# Sheet1.net
KiCad netlist of a schematic drawn in Altium Designer
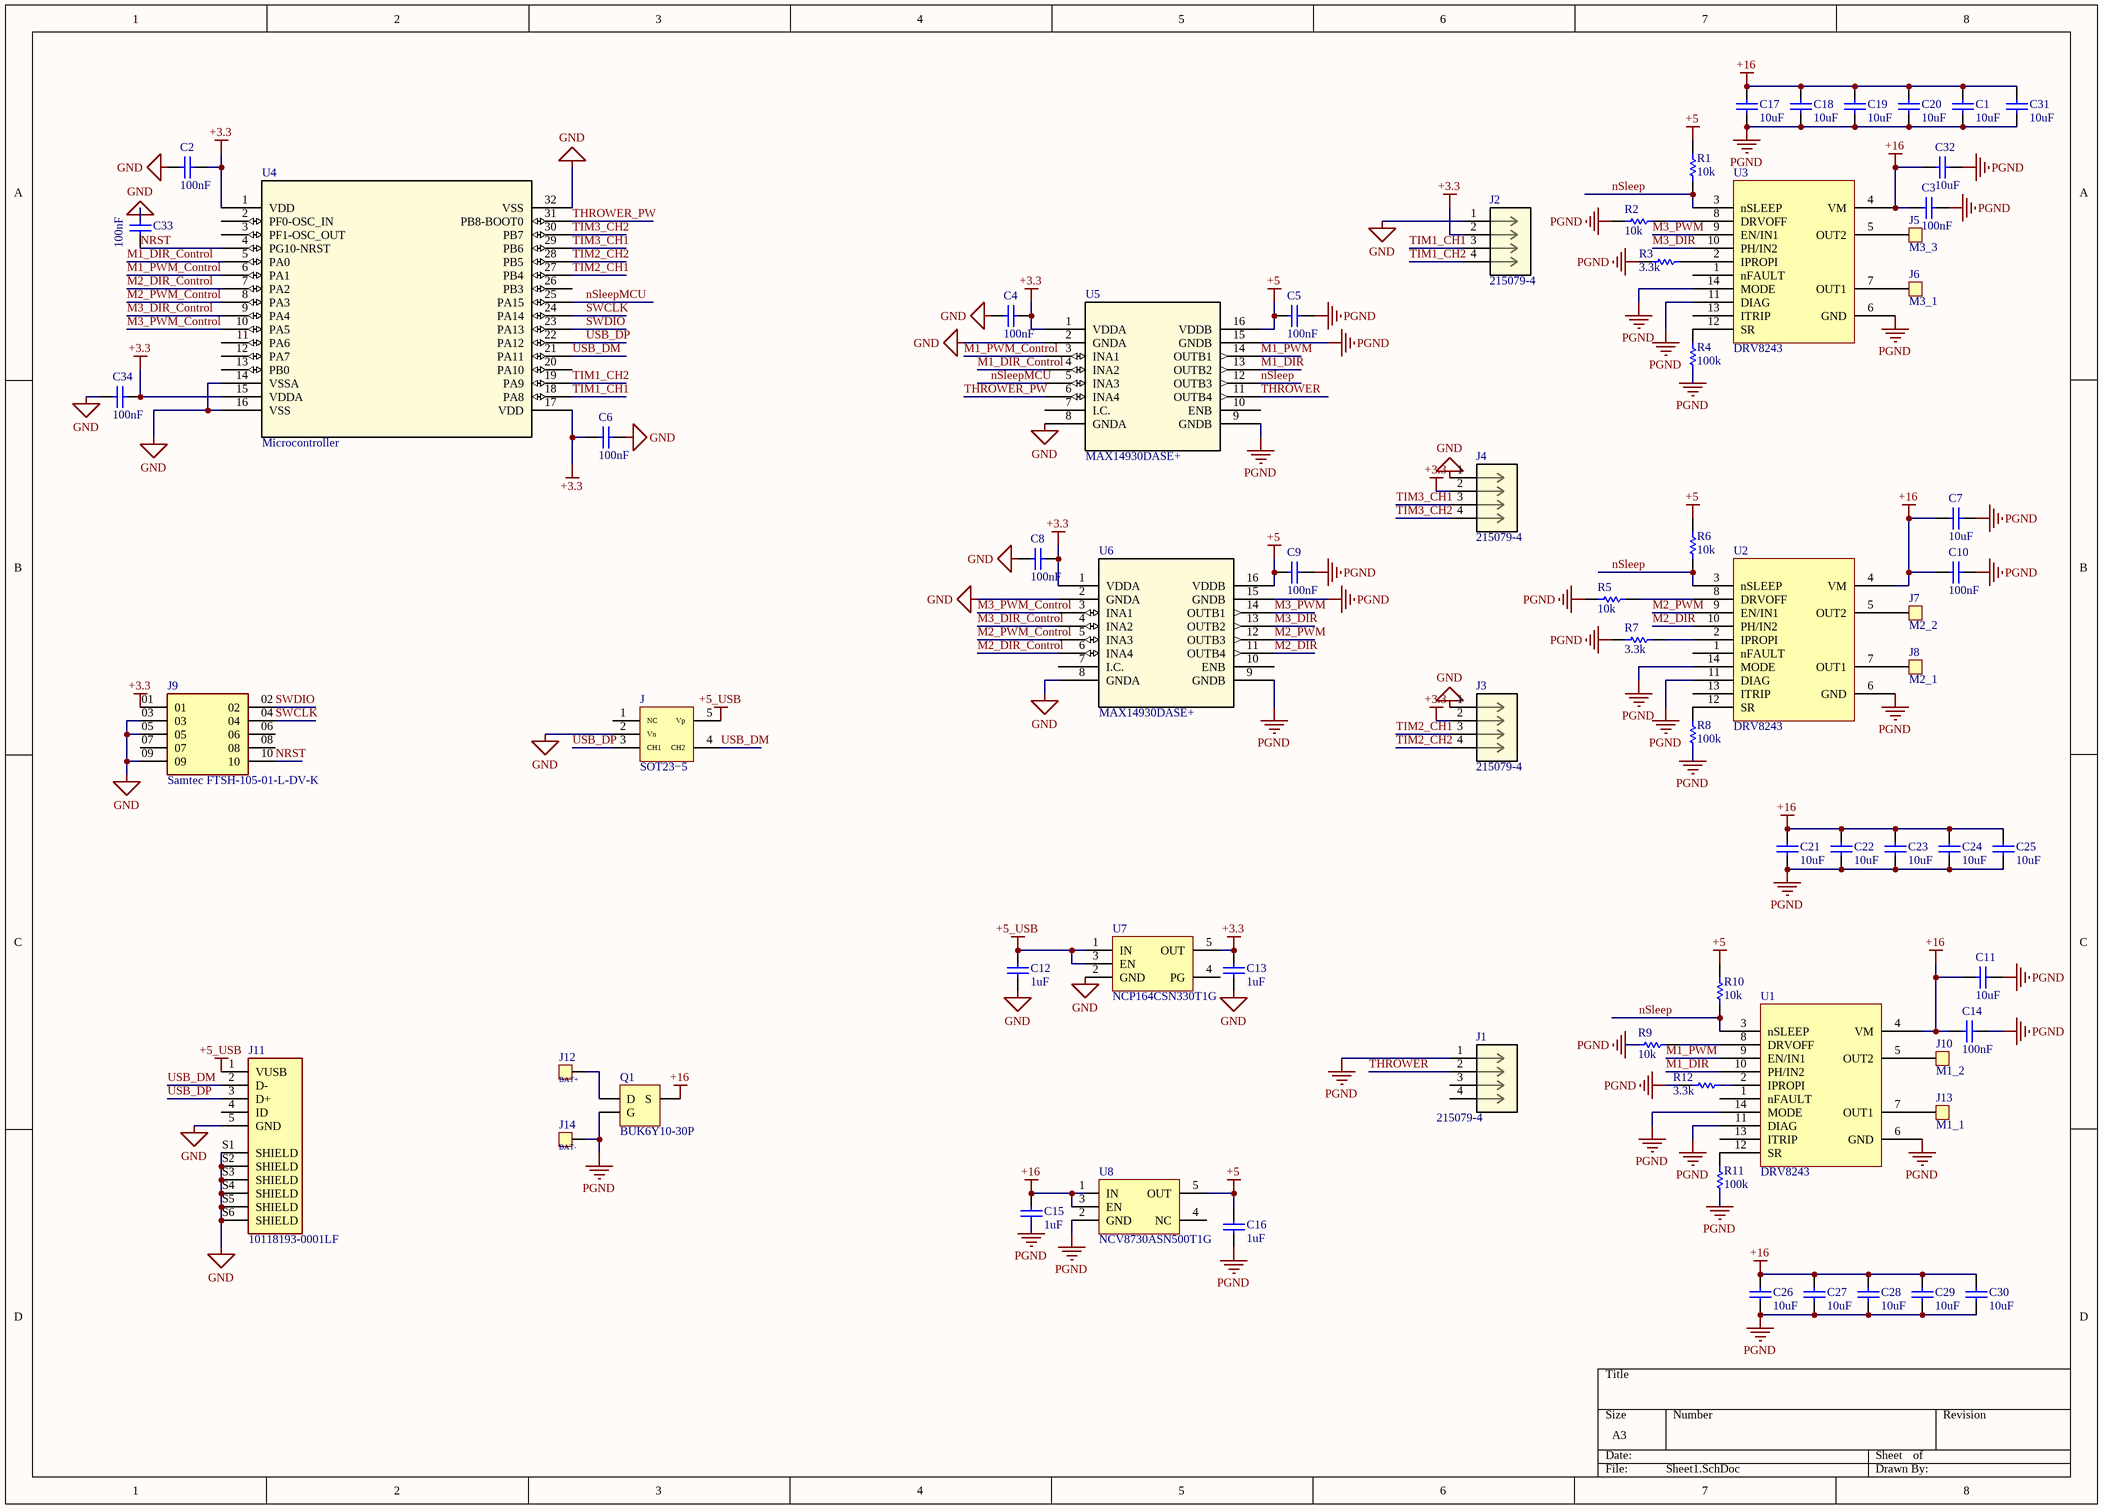
[diagram p0: Sheet1.SchDoc]

(export (version "E")
  (design (tool "Eeschema 10.0.6"))
  (components
    (comp (ref "C1")
      (value "10uF")
      (footprint "CAPC1206(3216)190_N")
      (description "CAP 10uF 25V -20% to +80% 1206 (3216 Metric) Thickness 1.9mm SMD")
      (fields (field (name "TOLERANCE") "-20% to +80%") (field (name "Comment") "CAP 10uF"))
      (libsource (lib "Altium Content Vault") (part "CAP"))
    )
    (comp (ref "C2")
      (value "100nF")
      (footprint "CAPC1608X90X35LL15T15")
      (fields
        (field (name "MANUFACTURER") "AVX Interconnect / Elco")
        (field (name "PART NUMBER") "06035C104J4Z2A")
      )
      (libsource (lib "Altium Content Vault") (part "CAP"))
    )
    (comp (ref "C3")
      (value "100nF")
      (footprint "CAPC1608X90X35LL15T15")
      (fields
        (field (name "MANUFACTURER") "AVX Interconnect / Elco")
        (field (name "PART NUMBER") "06035C104J4Z2A")
      )
      (libsource (lib "Altium Content Vault") (part "CAP"))
    )
    (comp (ref "C4")
      (value "100nF")
      (footprint "CAPC1608X90X35LL15T15")
      (fields
        (field (name "MANUFACTURER") "AVX Interconnect / Elco")
        (field (name "PART NUMBER") "06035C104J4Z2A")
      )
      (libsource (lib "Altium Content Vault") (part "CAP"))
    )
    (comp (ref "C5")
      (value "100nF")
      (footprint "CAPC1608X90X35LL15T15")
      (fields
        (field (name "MANUFACTURER") "AVX Interconnect / Elco")
        (field (name "PART NUMBER") "06035C104J4Z2A")
      )
      (libsource (lib "Altium Content Vault") (part "CAP"))
    )
    (comp (ref "C6")
      (value "100nF")
      (footprint "CAPC1608X90X35LL15T15")
      (fields
        (field (name "MANUFACTURER") "AVX Interconnect / Elco")
        (field (name "PART NUMBER") "06035C104J4Z2A")
      )
      (libsource (lib "Altium Content Vault") (part "CAP"))
    )
    (comp (ref "C7")
      (value "10uF")
      (footprint "CAPC1206(3216)190_N")
      (description "CAP 10uF 25V -20% to +80% 1206 (3216 Metric) Thickness 1.9mm SMD")
      (fields (field (name "TOLERANCE") "-20% to +80%") (field (name "Comment") "CAP 10uF"))
      (libsource (lib "Altium Content Vault") (part "CAP"))
    )
    (comp (ref "C8")
      (value "100nF")
      (footprint "CAPC1608X90X35LL15T15")
      (fields
        (field (name "MANUFACTURER") "AVX Interconnect / Elco")
        (field (name "PART NUMBER") "06035C104J4Z2A")
      )
      (libsource (lib "Altium Content Vault") (part "CAP"))
    )
    (comp (ref "C9")
      (value "100nF")
      (footprint "CAPC1608X90X35LL15T15")
      (fields
        (field (name "MANUFACTURER") "AVX Interconnect / Elco")
        (field (name "PART NUMBER") "06035C104J4Z2A")
      )
      (libsource (lib "Altium Content Vault") (part "CAP"))
    )
    (comp (ref "C10")
      (value "100nF")
      (footprint "CAPC1608X90X35LL15T15")
      (fields
        (field (name "MANUFACTURER") "AVX Interconnect / Elco")
        (field (name "PART NUMBER") "06035C104J4Z2A")
      )
      (libsource (lib "Altium Content Vault") (part "CAP"))
    )
    (comp (ref "C11")
      (value "10uF")
      (footprint "CAPC1206(3216)190_N")
      (description "CAP 10uF 25V -20% to +80% 1206 (3216 Metric) Thickness 1.9mm SMD")
      (fields (field (name "TOLERANCE") "-20% to +80%") (field (name "Comment") "CAP 10uF"))
      (libsource (lib "Altium Content Vault") (part "CAP"))
    )
    (comp (ref "C12")
      (value "1uF")
      (footprint "CAPC1608X90X35LL15T15")
      (fields
        (field (name "MANUFACTURER") "AVX Interconnect / Elco")
        (field (name "PART NUMBER") "06035C104J4Z2A")
      )
      (libsource (lib "Altium Content Vault") (part "CAP"))
    )
    (comp (ref "C13")
      (value "1uF")
      (footprint "CAPC1608X90X35LL15T15")
      (fields
        (field (name "MANUFACTURER") "AVX Interconnect / Elco")
        (field (name "PART NUMBER") "06035C104J4Z2A")
      )
      (libsource (lib "Altium Content Vault") (part "CAP"))
    )
    (comp (ref "C14")
      (value "100nF")
      (footprint "CAPC1608X90X35LL15T15")
      (fields
        (field (name "MANUFACTURER") "AVX Interconnect / Elco")
        (field (name "PART NUMBER") "06035C104J4Z2A")
      )
      (libsource (lib "Altium Content Vault") (part "CAP"))
    )
    (comp (ref "C15")
      (value "1uF")
      (footprint "CAPC1608X90X35LL15T15")
      (fields
        (field (name "MANUFACTURER") "AVX Interconnect / Elco")
        (field (name "PART NUMBER") "06035C104J4Z2A")
      )
      (libsource (lib "Altium Content Vault") (part "CAP"))
    )
    (comp (ref "C16")
      (value "1uF")
      (footprint "CAPC1608X90X35LL15T15")
      (fields
        (field (name "MANUFACTURER") "AVX Interconnect / Elco")
        (field (name "PART NUMBER") "06035C104J4Z2A")
      )
      (libsource (lib "Altium Content Vault") (part "CAP"))
    )
    (comp (ref "C17")
      (value "10uF")
      (footprint "CAPC1206(3216)190_N")
      (description "CAP 10uF 25V -20% to +80% 1206 (3216 Metric) Thickness 1.9mm SMD")
      (fields (field (name "TOLERANCE") "-20% to +80%") (field (name "Comment") "CAP 10uF"))
      (libsource (lib "Altium Content Vault") (part "CAP"))
    )
    (comp (ref "C18")
      (value "10uF")
      (footprint "CAPC1206(3216)190_N")
      (description "CAP 10uF 25V -20% to +80% 1206 (3216 Metric) Thickness 1.9mm SMD")
      (fields (field (name "TOLERANCE") "-20% to +80%") (field (name "Comment") "CAP 10uF"))
      (libsource (lib "Altium Content Vault") (part "CAP"))
    )
    (comp (ref "C19")
      (value "10uF")
      (footprint "CAPC1206(3216)190_N")
      (description "CAP 10uF 25V -20% to +80% 1206 (3216 Metric) Thickness 1.9mm SMD")
      (fields (field (name "TOLERANCE") "-20% to +80%") (field (name "Comment") "CAP 10uF"))
      (libsource (lib "Altium Content Vault") (part "CAP"))
    )
    (comp (ref "C20")
      (value "10uF")
      (footprint "CAPC1206(3216)190_N")
      (description "CAP 10uF 25V -20% to +80% 1206 (3216 Metric) Thickness 1.9mm SMD")
      (fields (field (name "TOLERANCE") "-20% to +80%") (field (name "Comment") "CAP 10uF"))
      (libsource (lib "Altium Content Vault") (part "CAP"))
    )
    (comp (ref "C21")
      (value "10uF")
      (footprint "CAPC1206(3216)190_N")
      (description "CAP 10uF 25V -20% to +80% 1206 (3216 Metric) Thickness 1.9mm SMD")
      (fields (field (name "TOLERANCE") "-20% to +80%") (field (name "Comment") "CAP 10uF"))
      (libsource (lib "Altium Content Vault") (part "CAP"))
    )
    (comp (ref "C22")
      (value "10uF")
      (footprint "CAPC1206(3216)190_N")
      (description "CAP 10uF 25V -20% to +80% 1206 (3216 Metric) Thickness 1.9mm SMD")
      (fields (field (name "TOLERANCE") "-20% to +80%") (field (name "Comment") "CAP 10uF"))
      (libsource (lib "Altium Content Vault") (part "CAP"))
    )
    (comp (ref "C23")
      (value "10uF")
      (footprint "CAPC1206(3216)190_N")
      (description "CAP 10uF 25V -20% to +80% 1206 (3216 Metric) Thickness 1.9mm SMD")
      (fields (field (name "TOLERANCE") "-20% to +80%") (field (name "Comment") "CAP 10uF"))
      (libsource (lib "Altium Content Vault") (part "CAP"))
    )
    (comp (ref "C24")
      (value "10uF")
      (footprint "CAPC1206(3216)190_N")
      (description "CAP 10uF 25V -20% to +80% 1206 (3216 Metric) Thickness 1.9mm SMD")
      (fields (field (name "TOLERANCE") "-20% to +80%") (field (name "Comment") "CAP 10uF"))
      (libsource (lib "Altium Content Vault") (part "CAP"))
    )
    (comp (ref "C25")
      (value "10uF")
      (footprint "CAPC1206(3216)190_N")
      (description "CAP 10uF 25V -20% to +80% 1206 (3216 Metric) Thickness 1.9mm SMD")
      (fields (field (name "TOLERANCE") "-20% to +80%") (field (name "Comment") "CAP 10uF"))
      (libsource (lib "Altium Content Vault") (part "CAP"))
    )
    (comp (ref "C26")
      (value "10uF")
      (footprint "CAPC1206(3216)190_N")
      (description "CAP 10uF 25V -20% to +80% 1206 (3216 Metric) Thickness 1.9mm SMD")
      (fields (field (name "TOLERANCE") "-20% to +80%") (field (name "Comment") "CAP 10uF"))
      (libsource (lib "Altium Content Vault") (part "CAP"))
    )
    (comp (ref "C27")
      (value "10uF")
      (footprint "CAPC1206(3216)190_N")
      (description "CAP 10uF 25V -20% to +80% 1206 (3216 Metric) Thickness 1.9mm SMD")
      (fields (field (name "TOLERANCE") "-20% to +80%") (field (name "Comment") "CAP 10uF"))
      (libsource (lib "Altium Content Vault") (part "CAP"))
    )
    (comp (ref "C28")
      (value "10uF")
      (footprint "CAPC1206(3216)190_N")
      (description "CAP 10uF 25V -20% to +80% 1206 (3216 Metric) Thickness 1.9mm SMD")
      (fields (field (name "TOLERANCE") "-20% to +80%") (field (name "Comment") "CAP 10uF"))
      (libsource (lib "Altium Content Vault") (part "CAP"))
    )
    (comp (ref "C29")
      (value "10uF")
      (footprint "CAPC1206(3216)190_N")
      (description "CAP 10uF 25V -20% to +80% 1206 (3216 Metric) Thickness 1.9mm SMD")
      (fields (field (name "TOLERANCE") "-20% to +80%") (field (name "Comment") "CAP 10uF"))
      (libsource (lib "Altium Content Vault") (part "CAP"))
    )
    (comp (ref "C30")
      (value "10uF")
      (footprint "CAPC1206(3216)190_N")
      (description "CAP 10uF 25V -20% to +80% 1206 (3216 Metric) Thickness 1.9mm SMD")
      (fields (field (name "TOLERANCE") "-20% to +80%") (field (name "Comment") "CAP 10uF"))
      (libsource (lib "Altium Content Vault") (part "CAP"))
    )
    (comp (ref "C31")
      (value "10uF")
      (footprint "CAPC1206(3216)190_N")
      (description "CAP 10uF 25V -20% to +80% 1206 (3216 Metric) Thickness 1.9mm SMD")
      (fields (field (name "TOLERANCE") "-20% to +80%") (field (name "Comment") "CAP 10uF"))
      (libsource (lib "Altium Content Vault") (part "CAP"))
    )
    (comp (ref "C32")
      (value "10uF")
      (footprint "CAPC1608X90X35LL15T15")
      (fields
        (field (name "MANUFACTURER") "AVX Interconnect / Elco")
        (field (name "PART NUMBER") "06035C104J4Z2A")
      )
      (libsource (lib "Altium Content Vault") (part "CAP"))
    )
    (comp (ref "C33")
      (value "100nF")
      (footprint "CAPC1608X90X35LL15T15")
      (fields
        (field (name "MANUFACTURER") "AVX Interconnect / Elco")
        (field (name "PART NUMBER") "06035C104J4Z2A")
      )
      (libsource (lib "Altium Content Vault") (part "CAP"))
    )
    (comp (ref "C34")
      (value "100nF")
      (footprint "CAPC1608X90X35LL15T15")
      (fields
        (field (name "MANUFACTURER") "AVX Interconnect / Elco")
        (field (name "PART NUMBER") "06035C104J4Z2A")
      )
      (libsource (lib "Altium Content Vault") (part "CAP"))
    )
    (comp (ref "J")
      (value "SOT23−5")
      (footprint "CM1223-02SO")
      (description "USB protection")
      (libsource (lib "Schlib1") (part "CM1223-02SO TVS diode array"))
    )
    (comp (ref "J1")
      (value "215079-4")
      (footprint "Micro-MaTch 215079-4")
      (description "Thrower ESC connector")
      (libsource (lib "Schlib1") (part "Micro-MaTch 215079-4_1"))
    )
    (comp (ref "J2")
      (value "215079-4")
      (footprint "Micro-MaTch 215079-4")
      (description "Encoder connectors")
      (libsource (lib "Schlib1") (part "Micro-MaTch 215079-4_1"))
    )
    (comp (ref "J3")
      (value "215079-4")
      (footprint "Micro-MaTch 215079-4")
      (description "Encoder connectors")
      (libsource (lib "Schlib1") (part "Micro-MaTch 215079-4_1"))
    )
    (comp (ref "J4")
      (value "215079-4")
      (footprint "Micro-MaTch 215079-4")
      (description "Encoder connectors")
      (libsource (lib "Schlib1") (part "Micro-MaTch 215079-4_1"))
    )
    (comp (ref "J5") (value "M3_3") (footprint "J") (libsource (lib "Schlib1") (part "J")))
    (comp (ref "J6") (value "M3_1") (footprint "J") (libsource (lib "Schlib1") (part "J")))
    (comp (ref "J7") (value "M2_2") (footprint "J") (libsource (lib "Schlib1") (part "J")))
    (comp (ref "J8") (value "M2_1") (footprint "J") (libsource (lib "Schlib1") (part "J")))
    (comp (ref "J9")
      (value "Samtec FTSH-105-01-L-DV-K")
      (footprint "Samtec FTSH-105-01-L-DV-K")
      (description "Programmer connector")
      (libsource (lib "Schlib1") (part "Samtec FTSH-105-01-L-DV-K"))
    )
    (comp (ref "J10") (value "M1_2") (footprint "J") (libsource (lib "Schlib1") (part "J")))
    (comp (ref "J11")
      (value "10118193-0001LF")
      (footprint "Amphenol 10118193-0001LF")
      (description "USB connector")
      (libsource (lib "Schlib1") (part "Amphenol 10118193-0001LF"))
    )
    (comp (ref "J12") (value "~") (footprint "J") (libsource (lib "") (part "J_1")))
    (comp (ref "J13") (value "M1_1") (footprint "J") (libsource (lib "Schlib1") (part "J")))
    (comp (ref "J14") (value "~") (footprint "J") (libsource (lib "") (part "J_1")))
    (comp (ref "Q1")
      (value "BUK6Y10-30P")
      (footprint "BUK6Y10-30P")
      (description "Reverse voltage protection")
      (libsource (lib "Schlib1") (part "BUK6Y10-30P"))
    )
    (comp (ref "R1")
      (value "ERJ3EKF1002V")
      (footprint "RESC1609X55X30LL15T15")
      (description "Chip Resistor, 10 KOhm, +/- 1%, 0.1 W, -55 to 155 degC, 0603 (1608 Metric), RoHS, Tape and Reel")
      (fields
        (field (name "RESISTANCE") "10k")
        (field (name "TOLERANCE") "1%")
        (field (name "MANUFACTURER") "Panasonic")
      )
      (libsource (lib "Altium Content Vault") (part "RES-2"))
    )
    (comp (ref "R2")
      (value "ERJ3EKF1002V")
      (footprint "RESC1609X55X30LL15T15")
      (description "Chip Resistor, 10 KOhm, +/- 1%, 0.1 W, -55 to 155 degC, 0603 (1608 Metric), RoHS, Tape and Reel")
      (fields
        (field (name "RESISTANCE") "10k")
        (field (name "TOLERANCE") "1%")
        (field (name "MANUFACTURER") "Panasonic")
      )
      (libsource (lib "Altium Content Vault") (part "RES-2"))
    )
    (comp (ref "R3")
      (value "3.3k")
      (footprint "RESC1608X55X30ML20T20")
      (fields (field (name "MANUFACTURER") "Panasonic") (field (name "PART NUMBER") "ERA3AEB332V"))
      (libsource (lib "Altium Content Vault") (part "RES"))
    )
    (comp (ref "R4")
      (value "100k")
      (footprint "RESC1608X55X30ML20T20")
      (fields (field (name "PART NUMBER") "ERA3AEB104V") (field (name "MANUFACTURER") "Panasonic"))
      (libsource (lib "Altium Content Vault") (part "RES"))
    )
    (comp (ref "R5")
      (value "ERJ3EKF1002V")
      (footprint "RESC1609X55X30LL15T15")
      (description "Chip Resistor, 10 KOhm, +/- 1%, 0.1 W, -55 to 155 degC, 0603 (1608 Metric), RoHS, Tape and Reel")
      (fields
        (field (name "RESISTANCE") "10k")
        (field (name "TOLERANCE") "1%")
        (field (name "MANUFACTURER") "Panasonic")
      )
      (libsource (lib "Altium Content Vault") (part "RES-2"))
    )
    (comp (ref "R6")
      (value "ERJ3EKF1002V")
      (footprint "RESC1609X55X30LL15T15")
      (description "Chip Resistor, 10 KOhm, +/- 1%, 0.1 W, -55 to 155 degC, 0603 (1608 Metric), RoHS, Tape and Reel")
      (fields
        (field (name "RESISTANCE") "10k")
        (field (name "TOLERANCE") "1%")
        (field (name "MANUFACTURER") "Panasonic")
      )
      (libsource (lib "Altium Content Vault") (part "RES-2"))
    )
    (comp (ref "R7")
      (value "3.3k")
      (footprint "RESC1608X55X30ML20T20")
      (fields (field (name "MANUFACTURER") "Panasonic") (field (name "PART NUMBER") "ERA3AEB332V"))
      (libsource (lib "Altium Content Vault") (part "RES"))
    )
    (comp (ref "R8")
      (value "100k")
      (footprint "RESC1608X55X30ML20T20")
      (fields (field (name "PART NUMBER") "ERA3AEB104V") (field (name "MANUFACTURER") "Panasonic"))
      (libsource (lib "Altium Content Vault") (part "RES"))
    )
    (comp (ref "R9")
      (value "ERJ3EKF1002V")
      (footprint "RESC1609X55X30LL15T15")
      (description "Chip Resistor, 10 KOhm, +/- 1%, 0.1 W, -55 to 155 degC, 0603 (1608 Metric), RoHS, Tape and Reel")
      (fields
        (field (name "RESISTANCE") "10k")
        (field (name "TOLERANCE") "1%")
        (field (name "MANUFACTURER") "Panasonic")
      )
      (libsource (lib "Altium Content Vault") (part "RES-2"))
    )
    (comp (ref "R10")
      (value "ERJ3EKF1002V")
      (footprint "RESC1609X55X30LL15T15")
      (description "Chip Resistor, 10 KOhm, +/- 1%, 0.1 W, -55 to 155 degC, 0603 (1608 Metric), RoHS, Tape and Reel")
      (fields
        (field (name "RESISTANCE") "10k")
        (field (name "TOLERANCE") "1%")
        (field (name "MANUFACTURER") "Panasonic")
      )
      (libsource (lib "Altium Content Vault") (part "RES-2"))
    )
    (comp (ref "R11")
      (value "100k")
      (footprint "RESC1608X55X30ML20T20")
      (fields (field (name "PART NUMBER") "ERA3AEB104V") (field (name "MANUFACTURER") "Panasonic"))
      (libsource (lib "Altium Content Vault") (part "RES"))
    )
    (comp (ref "R12")
      (value "3.3k")
      (footprint "RESC1608X55X30ML20T20")
      (fields (field (name "MANUFACTURER") "Panasonic") (field (name "PART NUMBER") "ERA3AEB332V"))
      (libsource (lib "Altium Content Vault") (part "RES"))
    )
    (comp (ref "U1")
      (value "DRV8243")
      (footprint "DRV8243")
      (description "DRV8243-Q1 Automotive H-Bridge Driver with Integrated Current Sense and Diagnostics")
      (libsource (lib "Schlib1") (part "DRV8243"))
    )
    (comp (ref "U2")
      (value "DRV8243")
      (footprint "DRV8243")
      (description "DRV8243-Q1 Automotive H-Bridge Driver with Integrated Current Sense and Diagnostics")
      (libsource (lib "Schlib1") (part "DRV8243"))
    )
    (comp (ref "U3")
      (value "DRV8243")
      (footprint "DRV8243")
      (description "DRV8243-Q1 Automotive H-Bridge Driver with Integrated Current Sense and Diagnostics")
      (libsource (lib "Schlib1") (part "DRV8243"))
    )
    (comp (ref "U4")
      (value "Microcontroller")
      (footprint "STM32G441KB")
      (libsource (lib "Schlib1") (part "STM32G441KBT3"))
    )
    (comp (ref "U5")
      (value "MAX14930DASE+")
      (footprint "MAX14930DASE+")
      (description "Isolator. Signals between the microcontroller and motor drivers should go through isolator(s).")
      (libsource (lib "Schlib1") (part "MAX14930DASE+"))
    )
    (comp (ref "U6")
      (value "MAX14930DASE+")
      (footprint "MAX14930DASE+")
      (description "Isolator. Signals between the microcontroller and motor drivers should go through isolator(s).")
      (libsource (lib "Schlib1") (part "MAX14930DASE+"))
    )
    (comp (ref "U7")
      (value "NCP164CSN330T1G")
      (footprint "NCV8730ASN500T1G")
      (libsource (lib "Schlib1") (part "NCP164CSN330T1G"))
    )
    (comp (ref "U8")
      (value "NCV8730ASN500T1G")
      (footprint "NCV8730ASN500T1G")
      (libsource (lib "Schlib1") (part "NCV8730ASN500T1G"))
    )
  )
  (nets
    (net (code "1") (name "+3.3") (class "Default")
      (node (ref "C13") (pin "1") (pinfunction "1_1") (pintype "passive"))
      (node (ref "C2") (pin "1") (pinfunction "1_1") (pintype "passive"))
      (node (ref "C34") (pin "1") (pinfunction "1_1") (pintype "passive"))
      (node (ref "C4") (pin "1") (pinfunction "1_1") (pintype "passive"))
      (node (ref "C6") (pin "2") (pinfunction "2_2") (pintype "passive"))
      (node (ref "C8") (pin "1") (pinfunction "1_1") (pintype "passive"))
      (node (ref "J2") (pin "2") (pinfunction "2_2") (pintype "passive"))
      (node (ref "J3") (pin "2") (pinfunction "2_2") (pintype "passive"))
      (node (ref "J4") (pin "2") (pinfunction "2_2") (pintype "passive"))
      (node (ref "J9") (pin "01") (pinfunction "01_01") (pintype "passive"))
      (node (ref "U4") (pin "1") (pinfunction "VDD_1") (pintype "power_in"))
      (node (ref "U4") (pin "15") (pinfunction "VDDA_15") (pintype "power_in"))
      (node (ref "U4") (pin "17") (pinfunction "VDD_17") (pintype "power_in"))
      (node (ref "U5") (pin "1") (pinfunction "VDDA_1") (pintype "power_in"))
      (node (ref "U6") (pin "1") (pinfunction "VDDA_1") (pintype "power_in"))
      (node (ref "U7") (pin "5") (pinfunction "OUT_5") (pintype "passive"))
    )
    (net (code "2") (name "+5") (class "Default")
      (node (ref "C16") (pin "1") (pinfunction "1_1") (pintype "passive"))
      (node (ref "C5") (pin "2") (pinfunction "2_2") (pintype "passive"))
      (node (ref "C9") (pin "2") (pinfunction "2_2") (pintype "passive"))
      (node (ref "R1") (pin "1") (pinfunction "1_1") (pintype "passive"))
      (node (ref "R10") (pin "1") (pinfunction "1_1") (pintype "passive"))
      (node (ref "R6") (pin "1") (pinfunction "1_1") (pintype "passive"))
      (node (ref "U5") (pin "16") (pinfunction "VDDB_16") (pintype "power_in"))
      (node (ref "U6") (pin "16") (pinfunction "VDDB_16") (pintype "power_in"))
      (node (ref "U8") (pin "5") (pinfunction "OUT_5") (pintype "passive"))
    )
    (net (code "3") (name "+5_USB") (class "Default")
      (node (ref "C12") (pin "1") (pinfunction "1_1") (pintype "passive"))
      (node (ref "J") (pin "5") (pinfunction "Vp_5") (pintype "passive"))
      (node (ref "J11") (pin "1") (pinfunction "VUSB_1") (pintype "passive"))
      (node (ref "U7") (pin "1") (pinfunction "IN_1") (pintype "passive"))
      (node (ref "U7") (pin "3") (pinfunction "EN_3") (pintype "passive"))
    )
    (net (code "4") (name "+16") (class "Default")
      (node (ref "C1") (pin "2") (pinfunction "2_2") (pintype "passive"))
      (node (ref "C10") (pin "2") (pinfunction "2_2") (pintype "passive"))
      (node (ref "C11") (pin "1") (pinfunction "1_1") (pintype "passive"))
      (node (ref "C14") (pin "2") (pinfunction "2_2") (pintype "passive"))
      (node (ref "C15") (pin "1") (pinfunction "1_1") (pintype "passive"))
      (node (ref "C17") (pin "2") (pinfunction "2_2") (pintype "passive"))
      (node (ref "C18") (pin "2") (pinfunction "2_2") (pintype "passive"))
      (node (ref "C19") (pin "2") (pinfunction "2_2") (pintype "passive"))
      (node (ref "C20") (pin "2") (pinfunction "2_2") (pintype "passive"))
      (node (ref "C21") (pin "2") (pinfunction "2_2") (pintype "passive"))
      (node (ref "C22") (pin "2") (pinfunction "2_2") (pintype "passive"))
      (node (ref "C23") (pin "2") (pinfunction "2_2") (pintype "passive"))
      (node (ref "C24") (pin "2") (pinfunction "2_2") (pintype "passive"))
      (node (ref "C25") (pin "2") (pinfunction "2_2") (pintype "passive"))
      (node (ref "C26") (pin "2") (pinfunction "2_2") (pintype "passive"))
      (node (ref "C27") (pin "2") (pinfunction "2_2") (pintype "passive"))
      (node (ref "C28") (pin "2") (pinfunction "2_2") (pintype "passive"))
      (node (ref "C29") (pin "2") (pinfunction "2_2") (pintype "passive"))
      (node (ref "C3") (pin "2") (pinfunction "2_2") (pintype "passive"))
      (node (ref "C30") (pin "2") (pinfunction "2_2") (pintype "passive"))
      (node (ref "C31") (pin "2") (pinfunction "2_2") (pintype "passive"))
      (node (ref "C32") (pin "2") (pinfunction "2_2") (pintype "passive"))
      (node (ref "C7") (pin "1") (pinfunction "1_1") (pintype "passive"))
      (node (ref "Q1") (pin "S") (pinfunction "S_S") (pintype "passive"))
      (node (ref "U1") (pin "4") (pinfunction "VM_4") (pintype "passive"))
      (node (ref "U2") (pin "4") (pinfunction "VM_4") (pintype "passive"))
      (node (ref "U3") (pin "4") (pinfunction "VM_4") (pintype "passive"))
      (node (ref "U8") (pin "1") (pinfunction "IN_1") (pintype "passive"))
      (node (ref "U8") (pin "3") (pinfunction "EN_3") (pintype "passive"))
    )
    (net (code "5") (name "/M1_DIR") (class "Default")
      (node (ref "U1") (pin "10") (pinfunction "PH/IN2_10") (pintype "passive"))
      (node (ref "U5") (pin "13") (pinfunction "OUTB2_13") (pintype "output"))
    )
    (net (code "6") (name "/M1_DIR_Control") (class "Default")
      (node (ref "U4") (pin "5") (pinfunction "PA0_5") (pintype "bidirectional"))
      (node (ref "U5") (pin "4") (pinfunction "INA2_4") (pintype "bidirectional"))
    )
    (net (code "7") (name "/M1_PWM") (class "Default")
      (node (ref "U1") (pin "9") (pinfunction "EN/IN1_9") (pintype "passive"))
      (node (ref "U5") (pin "14") (pinfunction "OUTB1_14") (pintype "output"))
    )
    (net (code "8") (name "/M1_PWM_Control") (class "Default")
      (node (ref "U4") (pin "6") (pinfunction "PA1_6") (pintype "bidirectional"))
      (node (ref "U5") (pin "3") (pinfunction "INA1_3") (pintype "bidirectional"))
    )
    (net (code "9") (name "/M2_DIR") (class "Default")
      (node (ref "U2") (pin "10") (pinfunction "PH/IN2_10") (pintype "passive"))
      (node (ref "U6") (pin "11") (pinfunction "OUTB4_11") (pintype "output"))
    )
    (net (code "10") (name "/M2_DIR_Control") (class "Default")
      (node (ref "U4") (pin "7") (pinfunction "PA2_7") (pintype "bidirectional"))
      (node (ref "U6") (pin "6") (pinfunction "INA4_6") (pintype "bidirectional"))
    )
    (net (code "11") (name "/M2_PWM") (class "Default")
      (node (ref "U2") (pin "9") (pinfunction "EN/IN1_9") (pintype "passive"))
      (node (ref "U6") (pin "12") (pinfunction "OUTB3_12") (pintype "output"))
    )
    (net (code "12") (name "/M2_PWM_Control") (class "Default")
      (node (ref "U4") (pin "8") (pinfunction "PA3_8") (pintype "bidirectional"))
      (node (ref "U6") (pin "5") (pinfunction "INA3_5") (pintype "bidirectional"))
    )
    (net (code "13") (name "/M3_DIR") (class "Default")
      (node (ref "U3") (pin "10") (pinfunction "PH/IN2_10") (pintype "passive"))
      (node (ref "U6") (pin "13") (pinfunction "OUTB2_13") (pintype "output"))
    )
    (net (code "14") (name "/M3_DIR_Control") (class "Default")
      (node (ref "U4") (pin "9") (pinfunction "PA4_9") (pintype "bidirectional"))
      (node (ref "U6") (pin "4") (pinfunction "INA2_4") (pintype "bidirectional"))
    )
    (net (code "15") (name "/M3_PWM") (class "Default")
      (node (ref "U3") (pin "9") (pinfunction "EN/IN1_9") (pintype "passive"))
      (node (ref "U6") (pin "14") (pinfunction "OUTB1_14") (pintype "output"))
    )
    (net (code "16") (name "/M3_PWM_Control") (class "Default")
      (node (ref "U4") (pin "10") (pinfunction "PA5_10") (pintype "bidirectional"))
      (node (ref "U6") (pin "3") (pinfunction "INA1_3") (pintype "bidirectional"))
    )
    (net (code "17") (name "/NRST") (class "Default")
      (node (ref "C33") (pin "2") (pinfunction "2_2") (pintype "passive"))
      (node (ref "J9") (pin "10") (pinfunction "10_10") (pintype "passive"))
      (node (ref "U4") (pin "4") (pinfunction "PG10-NRST_4") (pintype "bidirectional"))
    )
    (net (code "18") (name "/SWCLK") (class "Default")
      (node (ref "J9") (pin "04") (pinfunction "04_04") (pintype "passive"))
      (node (ref "U4") (pin "24") (pinfunction "PA14_24") (pintype "bidirectional"))
    )
    (net (code "19") (name "/SWDIO") (class "Default")
      (node (ref "J9") (pin "02") (pinfunction "02_02") (pintype "passive"))
      (node (ref "U4") (pin "23") (pinfunction "PA13_23") (pintype "bidirectional"))
    )
    (net (code "20") (name "/THROWER") (class "Default")
      (node (ref "J1") (pin "2") (pinfunction "2_2") (pintype "passive"))
      (node (ref "U5") (pin "11") (pinfunction "OUTB4_11") (pintype "output"))
    )
    (net (code "21") (name "/THROWER_PW") (class "Default")
      (node (ref "U4") (pin "31") (pinfunction "PB8-BOOT0_31") (pintype "bidirectional"))
      (node (ref "U5") (pin "6") (pinfunction "INA4_6") (pintype "bidirectional"))
    )
    (net (code "22") (name "/TIM1_CH1") (class "Default")
      (node (ref "J2") (pin "3") (pinfunction "3_3") (pintype "passive"))
      (node (ref "U4") (pin "18") (pinfunction "PA8_18") (pintype "bidirectional"))
    )
    (net (code "23") (name "/TIM1_CH2") (class "Default")
      (node (ref "J2") (pin "4") (pinfunction "4_4") (pintype "passive"))
      (node (ref "U4") (pin "19") (pinfunction "PA9_19") (pintype "bidirectional"))
    )
    (net (code "24") (name "/TIM2_CH1") (class "Default")
      (node (ref "J3") (pin "3") (pinfunction "3_3") (pintype "passive"))
      (node (ref "U4") (pin "27") (pinfunction "PB4_27") (pintype "bidirectional"))
    )
    (net (code "25") (name "/TIM2_CH2") (class "Default")
      (node (ref "J3") (pin "4") (pinfunction "4_4") (pintype "passive"))
      (node (ref "U4") (pin "28") (pinfunction "PB5_28") (pintype "bidirectional"))
    )
    (net (code "26") (name "/TIM3_CH1") (class "Default")
      (node (ref "J4") (pin "3") (pinfunction "3_3") (pintype "passive"))
      (node (ref "U4") (pin "29") (pinfunction "PB6_29") (pintype "bidirectional"))
    )
    (net (code "27") (name "/TIM3_CH2") (class "Default")
      (node (ref "J4") (pin "4") (pinfunction "4_4") (pintype "passive"))
      (node (ref "U4") (pin "30") (pinfunction "PB7_30") (pintype "bidirectional"))
    )
    (net (code "28") (name "/USB_DM") (class "Default")
      (node (ref "J") (pin "4") (pinfunction "CH2_4") (pintype "passive"))
      (node (ref "J11") (pin "2") (pinfunction "D-_2") (pintype "passive"))
      (node (ref "U4") (pin "21") (pinfunction "PA11_21") (pintype "bidirectional"))
    )
    (net (code "29") (name "/USB_DP") (class "Default")
      (node (ref "J") (pin "3") (pinfunction "CH1_3") (pintype "passive"))
      (node (ref "J11") (pin "3") (pinfunction "D+_3") (pintype "passive"))
      (node (ref "U4") (pin "22") (pinfunction "PA12_22") (pintype "bidirectional"))
    )
    (net (code "30") (name "/nSleep") (class "Default")
      (node (ref "R1") (pin "2") (pinfunction "2_2") (pintype "passive"))
      (node (ref "R10") (pin "2") (pinfunction "2_2") (pintype "passive"))
      (node (ref "R6") (pin "2") (pinfunction "2_2") (pintype "passive"))
      (node (ref "U1") (pin "3") (pinfunction "nSLEEP_3") (pintype "passive"))
      (node (ref "U2") (pin "3") (pinfunction "nSLEEP_3") (pintype "passive"))
      (node (ref "U3") (pin "3") (pinfunction "nSLEEP_3") (pintype "passive"))
      (node (ref "U5") (pin "12") (pinfunction "OUTB3_12") (pintype "output"))
    )
    (net (code "31") (name "/nSleepMCU") (class "Default")
      (node (ref "U4") (pin "25") (pinfunction "PA15_25") (pintype "bidirectional"))
      (node (ref "U5") (pin "5") (pinfunction "INA3_5") (pintype "bidirectional"))
    )
    (net (code "32") (name "GND") (class "Default")
      (node (ref "C12") (pin "2") (pinfunction "2_2") (pintype "passive"))
      (node (ref "C13") (pin "2") (pinfunction "2_2") (pintype "passive"))
      (node (ref "C2") (pin "2") (pinfunction "2_2") (pintype "passive"))
      (node (ref "C33") (pin "1") (pinfunction "1_1") (pintype "passive"))
      (node (ref "C34") (pin "2") (pinfunction "2_2") (pintype "passive"))
      (node (ref "C4") (pin "2") (pinfunction "2_2") (pintype "passive"))
      (node (ref "C6") (pin "1") (pinfunction "1_1") (pintype "passive"))
      (node (ref "C8") (pin "2") (pinfunction "2_2") (pintype "passive"))
      (node (ref "J") (pin "2") (pinfunction "Vn_2") (pintype "passive"))
      (node (ref "J11") (pin "5") (pinfunction "GND_5") (pintype "passive"))
      (node (ref "J11") (pin "S1") (pinfunction "SHIELD_S1") (pintype "passive"))
      (node (ref "J11") (pin "S2") (pinfunction "SHIELD_S2") (pintype "passive"))
      (node (ref "J11") (pin "S3") (pinfunction "SHIELD_S3") (pintype "passive"))
      (node (ref "J11") (pin "S4") (pinfunction "SHIELD_S4") (pintype "passive"))
      (node (ref "J11") (pin "S5") (pinfunction "SHIELD_S5") (pintype "passive"))
      (node (ref "J11") (pin "S6") (pinfunction "SHIELD_S6") (pintype "passive"))
      (node (ref "J2") (pin "1") (pinfunction "1_1") (pintype "passive"))
      (node (ref "J3") (pin "1") (pinfunction "1_1") (pintype "passive"))
      (node (ref "J4") (pin "1") (pinfunction "1_1") (pintype "passive"))
      (node (ref "J9") (pin "03") (pinfunction "03_03") (pintype "passive"))
      (node (ref "J9") (pin "05") (pinfunction "05_05") (pintype "passive"))
      (node (ref "J9") (pin "09") (pinfunction "09_09") (pintype "passive"))
      (node (ref "U4") (pin "14") (pinfunction "VSSA_14") (pintype "passive"))
      (node (ref "U4") (pin "16") (pinfunction "VSS_16") (pintype "passive"))
      (node (ref "U4") (pin "32") (pinfunction "VSS_32") (pintype "passive"))
      (node (ref "U5") (pin "2") (pinfunction "GNDA_2") (pintype "passive"))
      (node (ref "U5") (pin "8") (pinfunction "GNDA_8") (pintype "passive"))
      (node (ref "U6") (pin "2") (pinfunction "GNDA_2") (pintype "passive"))
      (node (ref "U6") (pin "8") (pinfunction "GNDA_8") (pintype "passive"))
      (node (ref "U7") (pin "2") (pinfunction "GND_2") (pintype "passive"))
    )
    (net (code "33") (name "Net-(J12-Pad1)") (class "Default")
      (node (ref "J12") (pin "1") (pinfunction "1_1") (pintype "passive"))
      (node (ref "Q1") (pin "D") (pinfunction "D_D") (pintype "passive"))
    )
    (net (code "34") (name "Net-(U1-DRVOFF)") (class "Default")
      (node (ref "R9") (pin "2") (pinfunction "2_2") (pintype "passive"))
      (node (ref "U1") (pin "8") (pinfunction "DRVOFF_8") (pintype "passive"))
    )
    (net (code "35") (name "Net-(U1-IPROPI)") (class "Default")
      (node (ref "R12") (pin "2") (pinfunction "2_2") (pintype "passive"))
      (node (ref "U1") (pin "2") (pinfunction "IPROPI_2") (pintype "passive"))
    )
    (net (code "36") (name "Net-(U1-OUT1)") (class "Default")
      (node (ref "J13") (pin "1") (pinfunction "1_1") (pintype "passive"))
      (node (ref "U1") (pin "7") (pinfunction "OUT1_7") (pintype "passive"))
    )
    (net (code "37") (name "Net-(U1-OUT2)") (class "Default")
      (node (ref "J10") (pin "1") (pinfunction "1_1") (pintype "passive"))
      (node (ref "U1") (pin "5") (pinfunction "OUT2_5") (pintype "passive"))
    )
    (net (code "38") (name "Net-(U1-SR)") (class "Default")
      (node (ref "R11") (pin "2") (pinfunction "2_2") (pintype "passive"))
      (node (ref "U1") (pin "12") (pinfunction "SR_12") (pintype "passive"))
    )
    (net (code "39") (name "Net-(U2-DRVOFF)") (class "Default")
      (node (ref "R5") (pin "2") (pinfunction "2_2") (pintype "passive"))
      (node (ref "U2") (pin "8") (pinfunction "DRVOFF_8") (pintype "passive"))
    )
    (net (code "40") (name "Net-(U2-IPROPI)") (class "Default")
      (node (ref "R7") (pin "2") (pinfunction "2_2") (pintype "passive"))
      (node (ref "U2") (pin "2") (pinfunction "IPROPI_2") (pintype "passive"))
    )
    (net (code "41") (name "Net-(U2-OUT1)") (class "Default")
      (node (ref "J8") (pin "1") (pinfunction "1_1") (pintype "passive"))
      (node (ref "U2") (pin "7") (pinfunction "OUT1_7") (pintype "passive"))
    )
    (net (code "42") (name "Net-(U2-OUT2)") (class "Default")
      (node (ref "J7") (pin "1") (pinfunction "1_1") (pintype "passive"))
      (node (ref "U2") (pin "5") (pinfunction "OUT2_5") (pintype "passive"))
    )
    (net (code "43") (name "Net-(U2-SR)") (class "Default")
      (node (ref "R8") (pin "2") (pinfunction "2_2") (pintype "passive"))
      (node (ref "U2") (pin "12") (pinfunction "SR_12") (pintype "passive"))
    )
    (net (code "44") (name "Net-(U3-DRVOFF)") (class "Default")
      (node (ref "R2") (pin "2") (pinfunction "2_2") (pintype "passive"))
      (node (ref "U3") (pin "8") (pinfunction "DRVOFF_8") (pintype "passive"))
    )
    (net (code "45") (name "Net-(U3-IPROPI)") (class "Default")
      (node (ref "R3") (pin "2") (pinfunction "2_2") (pintype "passive"))
      (node (ref "U3") (pin "2") (pinfunction "IPROPI_2") (pintype "passive"))
    )
    (net (code "46") (name "Net-(U3-OUT1)") (class "Default")
      (node (ref "J6") (pin "1") (pinfunction "1_1") (pintype "passive"))
      (node (ref "U3") (pin "7") (pinfunction "OUT1_7") (pintype "passive"))
    )
    (net (code "47") (name "Net-(U3-OUT2)") (class "Default")
      (node (ref "J5") (pin "1") (pinfunction "1_1") (pintype "passive"))
      (node (ref "U3") (pin "5") (pinfunction "OUT2_5") (pintype "passive"))
    )
    (net (code "48") (name "Net-(U3-SR)") (class "Default")
      (node (ref "R4") (pin "2") (pinfunction "2_2") (pintype "passive"))
      (node (ref "U3") (pin "12") (pinfunction "SR_12") (pintype "passive"))
    )
    (net (code "49") (name "PGND") (class "Default")
      (node (ref "C1") (pin "1") (pinfunction "1_1") (pintype "passive"))
      (node (ref "C10") (pin "1") (pinfunction "1_1") (pintype "passive"))
      (node (ref "C11") (pin "2") (pinfunction "2_2") (pintype "passive"))
      (node (ref "C14") (pin "1") (pinfunction "1_1") (pintype "passive"))
      (node (ref "C15") (pin "2") (pinfunction "2_2") (pintype "passive"))
      (node (ref "C16") (pin "2") (pinfunction "2_2") (pintype "passive"))
      (node (ref "C17") (pin "1") (pinfunction "1_1") (pintype "passive"))
      (node (ref "C18") (pin "1") (pinfunction "1_1") (pintype "passive"))
      (node (ref "C19") (pin "1") (pinfunction "1_1") (pintype "passive"))
      (node (ref "C20") (pin "1") (pinfunction "1_1") (pintype "passive"))
      (node (ref "C21") (pin "1") (pinfunction "1_1") (pintype "passive"))
      (node (ref "C22") (pin "1") (pinfunction "1_1") (pintype "passive"))
      (node (ref "C23") (pin "1") (pinfunction "1_1") (pintype "passive"))
      (node (ref "C24") (pin "1") (pinfunction "1_1") (pintype "passive"))
      (node (ref "C25") (pin "1") (pinfunction "1_1") (pintype "passive"))
      (node (ref "C26") (pin "1") (pinfunction "1_1") (pintype "passive"))
      (node (ref "C27") (pin "1") (pinfunction "1_1") (pintype "passive"))
      (node (ref "C28") (pin "1") (pinfunction "1_1") (pintype "passive"))
      (node (ref "C29") (pin "1") (pinfunction "1_1") (pintype "passive"))
      (node (ref "C3") (pin "1") (pinfunction "1_1") (pintype "passive"))
      (node (ref "C30") (pin "1") (pinfunction "1_1") (pintype "passive"))
      (node (ref "C31") (pin "1") (pinfunction "1_1") (pintype "passive"))
      (node (ref "C32") (pin "1") (pinfunction "1_1") (pintype "passive"))
      (node (ref "C5") (pin "1") (pinfunction "1_1") (pintype "passive"))
      (node (ref "C7") (pin "2") (pinfunction "2_2") (pintype "passive"))
      (node (ref "C9") (pin "1") (pinfunction "1_1") (pintype "passive"))
      (node (ref "J1") (pin "1") (pinfunction "1_1") (pintype "passive"))
      (node (ref "J14") (pin "1") (pinfunction "1_1") (pintype "passive"))
      (node (ref "Q1") (pin "G") (pinfunction "G_G") (pintype "passive"))
      (node (ref "R11") (pin "1") (pinfunction "1_1") (pintype "passive"))
      (node (ref "R12") (pin "1") (pinfunction "1_1") (pintype "passive"))
      (node (ref "R2") (pin "1") (pinfunction "1_1") (pintype "passive"))
      (node (ref "R3") (pin "1") (pinfunction "1_1") (pintype "passive"))
      (node (ref "R4") (pin "1") (pinfunction "1_1") (pintype "passive"))
      (node (ref "R5") (pin "1") (pinfunction "1_1") (pintype "passive"))
      (node (ref "R7") (pin "1") (pinfunction "1_1") (pintype "passive"))
      (node (ref "R8") (pin "1") (pinfunction "1_1") (pintype "passive"))
      (node (ref "R9") (pin "1") (pinfunction "1_1") (pintype "passive"))
      (node (ref "U1") (pin "11") (pinfunction "DIAG_11") (pintype "passive"))
      (node (ref "U1") (pin "14") (pinfunction "MODE_14") (pintype "passive"))
      (node (ref "U1") (pin "6") (pinfunction "GND_6") (pintype "passive"))
      (node (ref "U2") (pin "11") (pinfunction "DIAG_11") (pintype "passive"))
      (node (ref "U2") (pin "14") (pinfunction "MODE_14") (pintype "passive"))
      (node (ref "U2") (pin "6") (pinfunction "GND_6") (pintype "passive"))
      (node (ref "U3") (pin "11") (pinfunction "DIAG_11") (pintype "passive"))
      (node (ref "U3") (pin "14") (pinfunction "MODE_14") (pintype "passive"))
      (node (ref "U3") (pin "6") (pinfunction "GND_6") (pintype "passive"))
      (node (ref "U5") (pin "15") (pinfunction "GNDB_15") (pintype "passive"))
      (node (ref "U5") (pin "9") (pinfunction "GNDB_9") (pintype "passive"))
      (node (ref "U6") (pin "15") (pinfunction "GNDB_15") (pintype "passive"))
      (node (ref "U6") (pin "9") (pinfunction "GNDB_9") (pintype "passive"))
      (node (ref "U8") (pin "2") (pinfunction "GND_2") (pintype "passive"))
    )
    (net (code "50") (name "unconnected-(J-NC-Pad1)") (class "Default")
      (node (ref "J") (pin "1") (pinfunction "NC_1") (pintype "passive"))
    )
    (net (code "51") (name "unconnected-(J1-Pad3)") (class "Default")
      (node (ref "J1") (pin "3") (pinfunction "3_3") (pintype "passive"))
    )
    (net (code "52") (name "unconnected-(J1-Pad4)") (class "Default")
      (node (ref "J1") (pin "4") (pinfunction "4_4") (pintype "passive"))
    )
    (net (code "53") (name "unconnected-(J9-Pad06)") (class "Default")
      (node (ref "J9") (pin "06") (pinfunction "06_06") (pintype "passive"))
    )
    (net (code "54") (name "unconnected-(J9-Pad07)") (class "Default")
      (node (ref "J9") (pin "07") (pinfunction "07_07") (pintype "passive"))
    )
    (net (code "55") (name "unconnected-(J9-Pad08)") (class "Default")
      (node (ref "J9") (pin "08") (pinfunction "08_08") (pintype "passive"))
    )
    (net (code "56") (name "unconnected-(J11-ID-Pad4)") (class "Default")
      (node (ref "J11") (pin "4") (pinfunction "ID_4") (pintype "passive"))
    )
    (net (code "57") (name "unconnected-(U1-ITRIP-Pad13)") (class "Default")
      (node (ref "U1") (pin "13") (pinfunction "ITRIP_13") (pintype "passive"))
    )
    (net (code "58") (name "unconnected-(U1-nFAULT-Pad1)") (class "Default")
      (node (ref "U1") (pin "1") (pinfunction "nFAULT_1") (pintype "passive"))
    )
    (net (code "59") (name "unconnected-(U2-ITRIP-Pad13)") (class "Default")
      (node (ref "U2") (pin "13") (pinfunction "ITRIP_13") (pintype "passive"))
    )
    (net (code "60") (name "unconnected-(U2-nFAULT-Pad1)") (class "Default")
      (node (ref "U2") (pin "1") (pinfunction "nFAULT_1") (pintype "passive"))
    )
    (net (code "61") (name "unconnected-(U3-ITRIP-Pad13)") (class "Default")
      (node (ref "U3") (pin "13") (pinfunction "ITRIP_13") (pintype "passive"))
    )
    (net (code "62") (name "unconnected-(U3-nFAULT-Pad1)") (class "Default")
      (node (ref "U3") (pin "1") (pinfunction "nFAULT_1") (pintype "passive"))
    )
    (net (code "63") (name "unconnected-(U4-PA6-Pad11)") (class "Default")
      (node (ref "U4") (pin "11") (pinfunction "PA6_11") (pintype "bidirectional"))
    )
    (net (code "64") (name "unconnected-(U4-PA7-Pad12)") (class "Default")
      (node (ref "U4") (pin "12") (pinfunction "PA7_12") (pintype "bidirectional"))
    )
    (net (code "65") (name "unconnected-(U4-PA10-Pad20)") (class "Default")
      (node (ref "U4") (pin "20") (pinfunction "PA10_20") (pintype "bidirectional"))
    )
    (net (code "66") (name "unconnected-(U4-PB0-Pad13)") (class "Default")
      (node (ref "U4") (pin "13") (pinfunction "PB0_13") (pintype "bidirectional"))
    )
    (net (code "67") (name "unconnected-(U4-PB3-Pad26)") (class "Default")
      (node (ref "U4") (pin "26") (pinfunction "PB3_26") (pintype "bidirectional"))
    )
    (net (code "68") (name "unconnected-(U4-PF0-OSC_IN-Pad2)") (class "Default")
      (node (ref "U4") (pin "2") (pinfunction "PF0-OSC_IN_2") (pintype "bidirectional"))
    )
    (net (code "69") (name "unconnected-(U4-PF1-OSC_OUT-Pad3)") (class "Default")
      (node (ref "U4") (pin "3") (pinfunction "PF1-OSC_OUT_3") (pintype "bidirectional"))
    )
    (net (code "70") (name "unconnected-(U5-ENB-Pad10)") (class "Default")
      (node (ref "U5") (pin "10") (pinfunction "ENB_10") (pintype "passive"))
    )
    (net (code "71") (name "unconnected-(U5-I.C.-Pad7)") (class "Default")
      (node (ref "U5") (pin "7") (pinfunction "I.C._7") (pintype "passive"))
    )
    (net (code "72") (name "unconnected-(U6-ENB-Pad10)") (class "Default")
      (node (ref "U6") (pin "10") (pinfunction "ENB_10") (pintype "passive"))
    )
    (net (code "73") (name "unconnected-(U6-I.C.-Pad7)") (class "Default")
      (node (ref "U6") (pin "7") (pinfunction "I.C._7") (pintype "passive"))
    )
    (net (code "74") (name "unconnected-(U7-PG-Pad4)") (class "Default")
      (node (ref "U7") (pin "4") (pinfunction "PG_4") (pintype "passive"))
    )
    (net (code "75") (name "unconnected-(U8-NC-Pad4)") (class "Default")
      (node (ref "U8") (pin "4") (pinfunction "NC_4") (pintype "passive"))
    )
  )
)
